# FAE.net
KiCad netlist of a schematic drawn in EAGLE
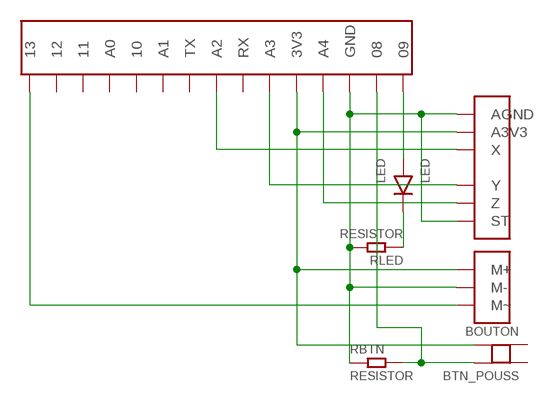
[diagram p0: schematic, sheet 1]

(export (version "E")
  (design (tool "Eeschema 10.0.6"))
  (components
    (comp (ref "BTN_POUSS")
      (value "BOUTON")
      (footprint "eagle-import:BOUTON")
      (libsource (lib "eagle-import") (part "BOUTON"))
    )
    (comp (ref "LED")
      (value "LED")
      (footprint "eagle-import:LED")
      (libsource (lib "eagle-import") (part "LED"))
    )
    (comp (ref "RBTN")
      (value "RESISTOR")
      (footprint "eagle-import:RESISTOR")
      (libsource (lib "eagle-import") (part "RESISTOR"))
    )
    (comp (ref "RLED")
      (value "RESISTOR")
      (footprint "eagle-import:RESISTOR")
      (libsource (lib "eagle-import") (part "RESISTOR"))
    )
    (comp (ref "U$1")
      (value "RAZOR_BOARD")
      (footprint "eagle-import:RAZOR_BOARD")
      (libsource (lib "eagle-import") (part "RAZOR_BOARD"))
    )
    (comp (ref "U$2")
      (value "ADXL377")
      (footprint "eagle-import:ADXL377")
      (libsource (lib "eagle-import") (part "ADXL377"))
    )
    (comp (ref "U$3")
      (value "SERVO_ADAPT")
      (footprint "eagle-import:SERVO_ADAPT")
      (libsource (lib "eagle-import") (part "SERVO_ADAPT"))
    )
  )
  (nets
    (net (code "1") (name "Net-(BTN_POUSS-PadC)") (class "Default")
      (node (ref "BTN_POUSS") (pin "C") (pinfunction "C_C") (pintype "bidirectional"))
      (node (ref "RBTN") (pin "B") (pinfunction "B_B") (pintype "bidirectional"))
      (node (ref "U$1") (pin "08") (pinfunction "08_08") (pintype "bidirectional"))
    )
    (net (code "2") (name "Net-(LED-PadIN)") (class "Default")
      (node (ref "LED") (pin "IN") (pinfunction "IN_IN") (pintype "input"))
      (node (ref "U$1") (pin "09") (pinfunction "09_09") (pintype "bidirectional"))
    )
    (net (code "3") (name "Net-(LED-PadOUT)") (class "Default")
      (node (ref "LED") (pin "OUT") (pinfunction "OUT_OUT") (pintype "output"))
      (node (ref "RLED") (pin "A") (pinfunction "A_A") (pintype "bidirectional"))
    )
    (net (code "4") (name "Net-(RBTN-PadA)") (class "Default")
      (node (ref "RBTN") (pin "A") (pinfunction "A_A") (pintype "bidirectional"))
      (node (ref "RLED") (pin "B") (pinfunction "B_B") (pintype "bidirectional"))
      (node (ref "U$1") (pin "GND") (pinfunction "GND_GND") (pintype "bidirectional"))
      (node (ref "U$2") (pin "AGND") (pinfunction "AGND_AGND") (pintype "bidirectional"))
      (node (ref "U$2") (pin "ST") (pinfunction "ST_ST") (pintype "bidirectional"))
      (node (ref "U$3") (pin "M-") (pinfunction "M-_M-") (pintype "bidirectional"))
    )
    (net (code "5") (name "Net-(U$1-PadA2)") (class "Default")
      (node (ref "U$1") (pin "A2") (pinfunction "A2_A2") (pintype "bidirectional"))
      (node (ref "U$2") (pin "X") (pinfunction "X_X") (pintype "bidirectional"))
    )
    (net (code "6") (name "Net-(U$1-PadA3)") (class "Default")
      (node (ref "U$1") (pin "A3") (pinfunction "A3_A3") (pintype "bidirectional"))
      (node (ref "U$2") (pin "Y") (pinfunction "Y_Y") (pintype "bidirectional"))
    )
    (net (code "7") (name "Net-(U$1-PadA4)") (class "Default")
      (node (ref "U$1") (pin "A4") (pinfunction "A4_A4") (pintype "bidirectional"))
      (node (ref "U$2") (pin "Z") (pinfunction "Z_Z") (pintype "bidirectional"))
    )
    (net (code "8") (name "Net-(U$2-A3V3)") (class "Default")
      (node (ref "BTN_POUSS") (pin "D") (pinfunction "D_D") (pintype "bidirectional"))
      (node (ref "U$1") (pin "3V3") (pinfunction "3V3_3V3") (pintype "bidirectional"))
      (node (ref "U$2") (pin "A3.3V") (pinfunction "A3V3_A3.3V") (pintype "bidirectional"))
      (node (ref "U$3") (pin "M+") (pinfunction "M+_M+") (pintype "bidirectional"))
    )
    (net (code "9") (name "Net-(U$3-M~{})") (class "Default")
      (node (ref "U$1") (pin "13") (pinfunction "13_13") (pintype "bidirectional"))
      (node (ref "U$3") (pin "M~") (pinfunction "M~{}_M~") (pintype "bidirectional"))
    )
    (net (code "10") (name "unconnected-(BTN_POUSS-PadA)") (class "Default")
      (node (ref "BTN_POUSS") (pin "A") (pinfunction "A_A") (pintype "bidirectional"))
    )
    (net (code "11") (name "unconnected-(BTN_POUSS-PadB)") (class "Default")
      (node (ref "BTN_POUSS") (pin "B") (pinfunction "B_B") (pintype "bidirectional"))
    )
    (net (code "12") (name "unconnected-(U$1-Pad10)") (class "Default")
      (node (ref "U$1") (pin "10") (pinfunction "10_10") (pintype "bidirectional"))
    )
    (net (code "13") (name "unconnected-(U$1-Pad11)") (class "Default")
      (node (ref "U$1") (pin "11") (pinfunction "11_11") (pintype "bidirectional"))
    )
    (net (code "14") (name "unconnected-(U$1-Pad12)") (class "Default")
      (node (ref "U$1") (pin "12") (pinfunction "12_12") (pintype "bidirectional"))
    )
    (net (code "15") (name "unconnected-(U$1-PadA0)") (class "Default")
      (node (ref "U$1") (pin "A0") (pinfunction "A0_A0") (pintype "bidirectional"))
    )
    (net (code "16") (name "unconnected-(U$1-PadA1)") (class "Default")
      (node (ref "U$1") (pin "A1") (pinfunction "A1_A1") (pintype "bidirectional"))
    )
    (net (code "17") (name "unconnected-(U$1-PadRX)") (class "Default")
      (node (ref "U$1") (pin "RX") (pinfunction "RX_RX") (pintype "bidirectional"))
    )
    (net (code "18") (name "unconnected-(U$1-PadTX)") (class "Default")
      (node (ref "U$1") (pin "TX") (pinfunction "TX_TX") (pintype "bidirectional"))
    )
  )
)
